# LinCorrector1.net
KiCad netlist of a schematic drawn in EAGLE
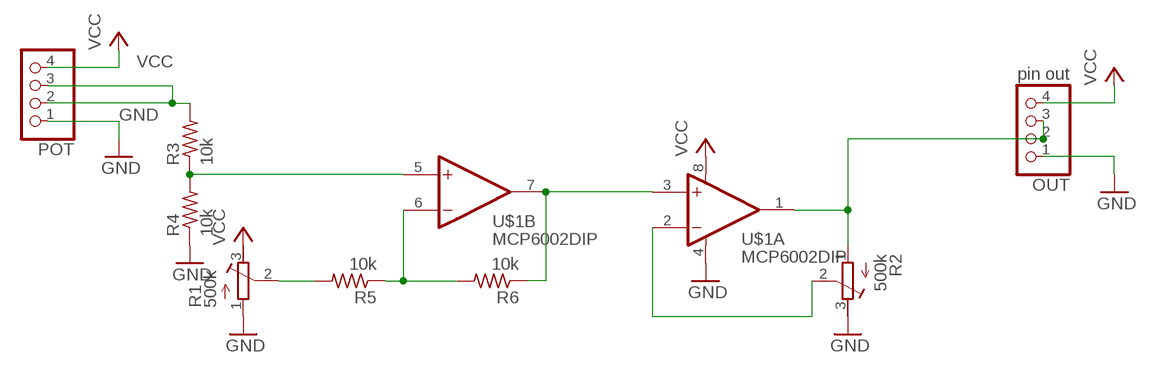
[diagram p0: schematic, sheet 1]

(export (version "E")
  (design (tool "Eeschema 10.0.6"))
  (components
    (comp (ref "OUT")
      (value "pin out")
      (footprint "eagle-import:1X04_90")
      (libsource (lib "eagle-import") (part "PINHD-1X4/90"))
    )
    (comp (ref "POT")
      (value "PINHD-1X4/90")
      (footprint "eagle-import:1X04_90")
      (libsource (lib "eagle-import") (part "PINHD-1X4/90"))
    )
    (comp (ref "R1")
      (value "500k")
      (footprint "eagle-import:RTRIM3296W")
      (libsource (lib "eagle-import") (part "R-TRIMM3296W"))
    )
    (comp (ref "R2")
      (value "500k")
      (footprint "eagle-import:RTRIM3296W")
      (libsource (lib "eagle-import") (part "R-TRIMM3296W"))
    )
    (comp (ref "R3")
      (value "10k")
      (footprint "eagle-import:0204_7")
      (libsource (lib "eagle-import") (part "R-US_0204/7"))
    )
    (comp (ref "R4")
      (value "10k")
      (footprint "eagle-import:0204_7")
      (libsource (lib "eagle-import") (part "R-US_0204/7"))
    )
    (comp (ref "R5")
      (value "10k")
      (footprint "eagle-import:0204_7")
      (libsource (lib "eagle-import") (part "R-US_0204/7"))
    )
    (comp (ref "R6")
      (value "10k")
      (footprint "eagle-import:0204_7")
      (libsource (lib "eagle-import") (part "R-US_0204/7"))
    )
    (comp (ref "U$1")
      (value "MCP6002DIP")
      (footprint "eagle-import:DIP-8")
      (libsource (lib "eagle-import") (part "MCP6002DIP"))
    )
  )
  (nets
    (net (code "1") (name "GND") (class "Default")
      (node (ref "OUT") (pin "1") (pinfunction "1_1") (pintype "passive"))
      (node (ref "POT") (pin "1") (pinfunction "1_1") (pintype "passive"))
      (node (ref "R1") (pin "1") (pinfunction "A_1") (pintype "passive"))
      (node (ref "R2") (pin "3") (pinfunction "E_3") (pintype "passive"))
      (node (ref "R4") (pin "1") (pinfunction "1_1") (pintype "passive"))
      (node (ref "U$1") (pin "4") (pinfunction "V-_4") (pintype "power_in"))
    )
    (net (code "2") (name "Net-(POT-Pad2)") (class "Default")
      (node (ref "POT") (pin "2") (pinfunction "2_2") (pintype "passive"))
      (node (ref "POT") (pin "3") (pinfunction "3_3") (pintype "passive"))
      (node (ref "R3") (pin "2") (pinfunction "2_2") (pintype "passive"))
    )
    (net (code "3") (name "Net-(R1-S)") (class "Default")
      (node (ref "R1") (pin "2") (pinfunction "S_2") (pintype "passive"))
      (node (ref "R5") (pin "2") (pinfunction "2_2") (pintype "passive"))
    )
    (net (code "4") (name "Net-(R2-A)") (class "Default")
      (node (ref "OUT") (pin "2") (pinfunction "2_2") (pintype "passive"))
      (node (ref "OUT") (pin "3") (pinfunction "3_3") (pintype "passive"))
      (node (ref "R2") (pin "1") (pinfunction "A_1") (pintype "passive"))
      (node (ref "U$1") (pin "1") (pinfunction "OUT_1") (pintype "output"))
    )
    (net (code "5") (name "Net-(R2-S)") (class "Default")
      (node (ref "R2") (pin "2") (pinfunction "S_2") (pintype "passive"))
      (node (ref "U$1") (pin "2") (pinfunction "-IN_2") (pintype "input"))
    )
    (net (code "6") (name "Net-(U$1A-+IN)") (class "Default")
      (node (ref "R6") (pin "1") (pinfunction "1_1") (pintype "passive"))
      (node (ref "U$1") (pin "3") (pinfunction "+IN_3") (pintype "input"))
      (node (ref "U$1") (pin "7") (pinfunction "OUT_7") (pintype "output"))
    )
    (net (code "7") (name "Net-(U$1B-+IN)") (class "Default")
      (node (ref "R3") (pin "1") (pinfunction "1_1") (pintype "passive"))
      (node (ref "R4") (pin "2") (pinfunction "2_2") (pintype "passive"))
      (node (ref "U$1") (pin "5") (pinfunction "+IN_5") (pintype "input"))
    )
    (net (code "8") (name "Net-(U$1B--IN)") (class "Default")
      (node (ref "R5") (pin "1") (pinfunction "1_1") (pintype "passive"))
      (node (ref "R6") (pin "2") (pinfunction "2_2") (pintype "passive"))
      (node (ref "U$1") (pin "6") (pinfunction "-IN_6") (pintype "input"))
    )
    (net (code "9") (name "VCC") (class "Default")
      (node (ref "OUT") (pin "4") (pinfunction "4_4") (pintype "passive"))
      (node (ref "POT") (pin "4") (pinfunction "4_4") (pintype "passive"))
      (node (ref "R1") (pin "3") (pinfunction "E_3") (pintype "passive"))
      (node (ref "U$1") (pin "8") (pinfunction "V+_8") (pintype "power_in"))
    )
  )
)
